# 5vAc_Dc.net
KiCad netlist of a schematic drawn in EAGLE
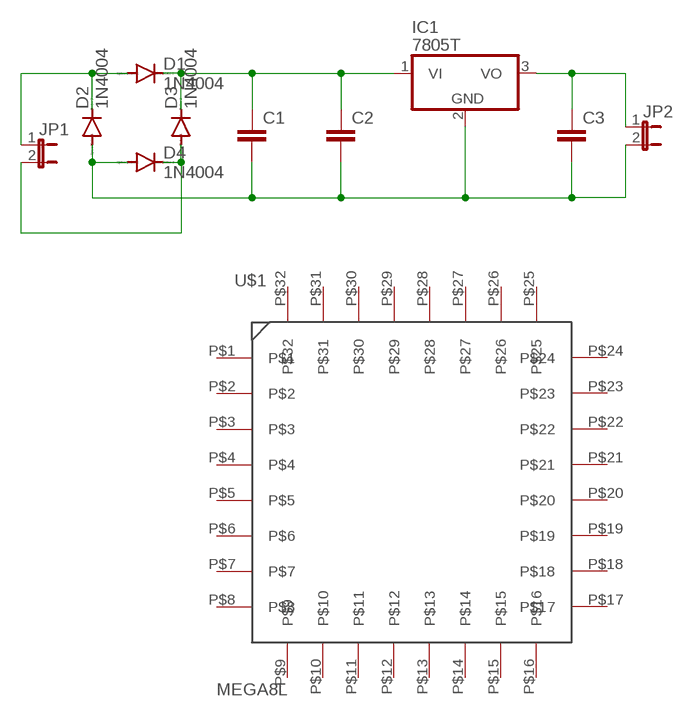
[diagram p0: schematic, sheet 1]

(export (version "E")
  (design (tool "Eeschema 10.0.6"))
  (components
    (comp (ref "C1")
      (value "C2,5-3")
      (footprint "eagle-import:C2.5-3")
      (libsource (lib "eagle-import") (part "C2,5-3"))
    )
    (comp (ref "C2")
      (value "C2,5-3")
      (footprint "eagle-import:C2.5-3")
      (libsource (lib "eagle-import") (part "C2,5-3"))
    )
    (comp (ref "C3")
      (value "C2,5-3")
      (footprint "eagle-import:C2.5-3")
      (libsource (lib "eagle-import") (part "C2,5-3"))
    )
    (comp (ref "D1")
      (value "1N4004")
      (footprint "eagle-import:DO41-10")
      (libsource (lib "eagle-import") (part "1N4004"))
    )
    (comp (ref "D2")
      (value "1N4004")
      (footprint "eagle-import:DO41-10")
      (libsource (lib "eagle-import") (part "1N4004"))
    )
    (comp (ref "D3")
      (value "1N4004")
      (footprint "eagle-import:DO41-10")
      (libsource (lib "eagle-import") (part "1N4004"))
    )
    (comp (ref "D4")
      (value "1N4004")
      (footprint "eagle-import:DO41-10")
      (libsource (lib "eagle-import") (part "1N4004"))
    )
    (comp (ref "IC1")
      (value "7805T")
      (footprint "eagle-import:TO220H")
      (libsource (lib "eagle-import") (part "78T05"))
    )
    (comp (ref "JP1")
      (value "JP1E")
      (footprint "eagle-import:JP1")
      (libsource (lib "eagle-import") (part "JP1E"))
    )
    (comp (ref "JP2")
      (value "JP1E")
      (footprint "eagle-import:JP1")
      (libsource (lib "eagle-import") (part "JP1E"))
    )
    (comp (ref "U$1")
      (value "MEGA8L")
      (footprint "eagle-import:TQFP_MEGA8L")
      (libsource (lib "eagle-import") (part "MEGA8L"))
    )
  )
  (nets
    (net (code "1") (name "Net-(D1-PadA)") (class "Default")
      (node (ref "D1") (pin "A") (pinfunction "A_A") (pintype "passive"))
      (node (ref "D2") (pin "C") (pinfunction "C_C") (pintype "passive"))
      (node (ref "JP1") (pin "1") (pinfunction "1_1") (pintype "passive"))
    )
    (net (code "2") (name "Net-(D3-PadA)") (class "Default")
      (node (ref "D3") (pin "A") (pinfunction "A_A") (pintype "passive"))
      (node (ref "D4") (pin "C") (pinfunction "C_C") (pintype "passive"))
      (node (ref "JP1") (pin "2") (pinfunction "2_2") (pintype "passive"))
    )
    (net (code "3") (name "Net-(IC1-GND)") (class "Default")
      (node (ref "C1") (pin "2") (pinfunction "2_2") (pintype "passive"))
      (node (ref "C2") (pin "2") (pinfunction "2_2") (pintype "passive"))
      (node (ref "C3") (pin "2") (pinfunction "2_2") (pintype "passive"))
      (node (ref "D2") (pin "A") (pinfunction "A_A") (pintype "passive"))
      (node (ref "D4") (pin "A") (pinfunction "A_A") (pintype "passive"))
      (node (ref "IC1") (pin "2") (pinfunction "GND_2") (pintype "passive"))
      (node (ref "JP2") (pin "2") (pinfunction "2_2") (pintype "passive"))
    )
    (net (code "4") (name "Net-(IC1-VI)") (class "Default")
      (node (ref "C1") (pin "1") (pinfunction "1_1") (pintype "passive"))
      (node (ref "C2") (pin "1") (pinfunction "1_1") (pintype "passive"))
      (node (ref "D1") (pin "C") (pinfunction "C_C") (pintype "passive"))
      (node (ref "D3") (pin "C") (pinfunction "C_C") (pintype "passive"))
      (node (ref "IC1") (pin "1") (pinfunction "VI_1") (pintype "input"))
    )
    (net (code "5") (name "Net-(IC1-VO)") (class "Default")
      (node (ref "C3") (pin "1") (pinfunction "1_1") (pintype "passive"))
      (node (ref "IC1") (pin "3") (pinfunction "VO_3") (pintype "passive"))
      (node (ref "JP2") (pin "1") (pinfunction "1_1") (pintype "passive"))
    )
    (net (code "6") (name "unconnected-(U$1-PadP$1)") (class "Default")
      (node (ref "U$1") (pin "P$1") (pinfunction "P$1_P$1") (pintype "bidirectional"))
    )
    (net (code "7") (name "unconnected-(U$1-PadP$2)") (class "Default")
      (node (ref "U$1") (pin "P$2") (pinfunction "P$2_P$2") (pintype "bidirectional"))
    )
    (net (code "8") (name "unconnected-(U$1-PadP$3)") (class "Default")
      (node (ref "U$1") (pin "P$3") (pinfunction "P$3_P$3") (pintype "bidirectional"))
    )
    (net (code "9") (name "unconnected-(U$1-PadP$4)") (class "Default")
      (node (ref "U$1") (pin "P$4") (pinfunction "P$4_P$4") (pintype "bidirectional"))
    )
    (net (code "10") (name "unconnected-(U$1-PadP$5)") (class "Default")
      (node (ref "U$1") (pin "P$5") (pinfunction "P$5_P$5") (pintype "bidirectional"))
    )
    (net (code "11") (name "unconnected-(U$1-PadP$6)") (class "Default")
      (node (ref "U$1") (pin "P$6") (pinfunction "P$6_P$6") (pintype "bidirectional"))
    )
    (net (code "12") (name "unconnected-(U$1-PadP$7)") (class "Default")
      (node (ref "U$1") (pin "P$7") (pinfunction "P$7_P$7") (pintype "bidirectional"))
    )
    (net (code "13") (name "unconnected-(U$1-PadP$8)") (class "Default")
      (node (ref "U$1") (pin "P$8") (pinfunction "P$8_P$8") (pintype "bidirectional"))
    )
    (net (code "14") (name "unconnected-(U$1-PadP$9)") (class "Default")
      (node (ref "U$1") (pin "P$9") (pinfunction "P$9_P$9") (pintype "bidirectional"))
    )
    (net (code "15") (name "unconnected-(U$1-PadP$10)") (class "Default")
      (node (ref "U$1") (pin "P$10") (pinfunction "P$10_P$10") (pintype "bidirectional"))
    )
    (net (code "16") (name "unconnected-(U$1-PadP$11)") (class "Default")
      (node (ref "U$1") (pin "P$11") (pinfunction "P$11_P$11") (pintype "bidirectional"))
    )
    (net (code "17") (name "unconnected-(U$1-PadP$12)") (class "Default")
      (node (ref "U$1") (pin "P$12") (pinfunction "P$12_P$12") (pintype "bidirectional"))
    )
    (net (code "18") (name "unconnected-(U$1-PadP$13)") (class "Default")
      (node (ref "U$1") (pin "P$13") (pinfunction "P$13_P$13") (pintype "bidirectional"))
    )
    (net (code "19") (name "unconnected-(U$1-PadP$14)") (class "Default")
      (node (ref "U$1") (pin "P$14") (pinfunction "P$14_P$14") (pintype "bidirectional"))
    )
    (net (code "20") (name "unconnected-(U$1-PadP$15)") (class "Default")
      (node (ref "U$1") (pin "P$15") (pinfunction "P$15_P$15") (pintype "bidirectional"))
    )
    (net (code "21") (name "unconnected-(U$1-PadP$16)") (class "Default")
      (node (ref "U$1") (pin "P$16") (pinfunction "P$16_P$16") (pintype "bidirectional"))
    )
    (net (code "22") (name "unconnected-(U$1-PadP$17)") (class "Default")
      (node (ref "U$1") (pin "P$17") (pinfunction "P$17_P$17") (pintype "bidirectional"))
    )
    (net (code "23") (name "unconnected-(U$1-PadP$18)") (class "Default")
      (node (ref "U$1") (pin "P$18") (pinfunction "P$18_P$18") (pintype "bidirectional"))
    )
    (net (code "24") (name "unconnected-(U$1-PadP$19)") (class "Default")
      (node (ref "U$1") (pin "P$19") (pinfunction "P$19_P$19") (pintype "bidirectional"))
    )
    (net (code "25") (name "unconnected-(U$1-PadP$20)") (class "Default")
      (node (ref "U$1") (pin "P$20") (pinfunction "P$20_P$20") (pintype "bidirectional"))
    )
    (net (code "26") (name "unconnected-(U$1-PadP$21)") (class "Default")
      (node (ref "U$1") (pin "P$21") (pinfunction "P$21_P$21") (pintype "bidirectional"))
    )
    (net (code "27") (name "unconnected-(U$1-PadP$22)") (class "Default")
      (node (ref "U$1") (pin "P$22") (pinfunction "P$22_P$22") (pintype "bidirectional"))
    )
    (net (code "28") (name "unconnected-(U$1-PadP$23)") (class "Default")
      (node (ref "U$1") (pin "P$23") (pinfunction "P$23_P$23") (pintype "bidirectional"))
    )
    (net (code "29") (name "unconnected-(U$1-PadP$24)") (class "Default")
      (node (ref "U$1") (pin "P$24") (pinfunction "P$24_P$24") (pintype "bidirectional"))
    )
    (net (code "30") (name "unconnected-(U$1-PadP$25)") (class "Default")
      (node (ref "U$1") (pin "P$25") (pinfunction "P$25_P$25") (pintype "bidirectional"))
    )
    (net (code "31") (name "unconnected-(U$1-PadP$26)") (class "Default")
      (node (ref "U$1") (pin "P$26") (pinfunction "P$26_P$26") (pintype "bidirectional"))
    )
    (net (code "32") (name "unconnected-(U$1-PadP$27)") (class "Default")
      (node (ref "U$1") (pin "P$27") (pinfunction "P$27_P$27") (pintype "bidirectional"))
    )
    (net (code "33") (name "unconnected-(U$1-PadP$28)") (class "Default")
      (node (ref "U$1") (pin "P$28") (pinfunction "P$28_P$28") (pintype "bidirectional"))
    )
    (net (code "34") (name "unconnected-(U$1-PadP$29)") (class "Default")
      (node (ref "U$1") (pin "P$29") (pinfunction "P$29_P$29") (pintype "bidirectional"))
    )
    (net (code "35") (name "unconnected-(U$1-PadP$30)") (class "Default")
      (node (ref "U$1") (pin "P$30") (pinfunction "P$30_P$30") (pintype "bidirectional"))
    )
    (net (code "36") (name "unconnected-(U$1-PadP$31)") (class "Default")
      (node (ref "U$1") (pin "P$31") (pinfunction "P$31_P$31") (pintype "bidirectional"))
    )
    (net (code "37") (name "unconnected-(U$1-PadP$32)") (class "Default")
      (node (ref "U$1") (pin "P$32") (pinfunction "P$32_P$32") (pintype "bidirectional"))
    )
  )
)
